# Memory_Address_Register_Connector.net
KiCad netlist of a schematic drawn in Altium Designer
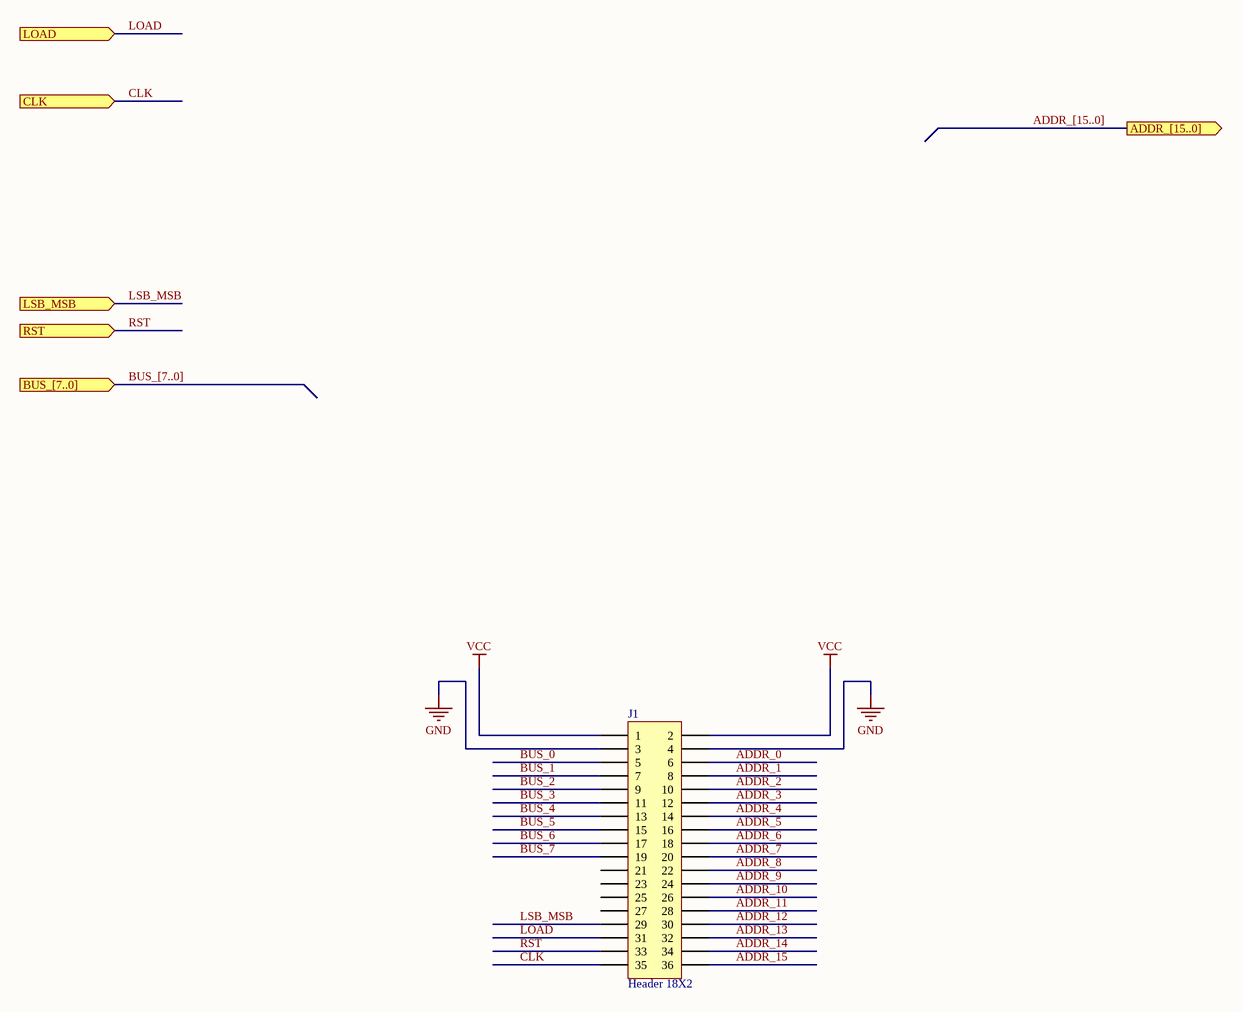
[diagram p0: Memory Address Register Connector.SchDoc]

(export (version "E")
  (design (tool "Eeschema 10.0.6"))
  (components
    (comp (ref "J1")
      (value "Header 18X2")
      (footprint "HDR2X18")
      (description "Header, 18-Pin, Dual row")
      (fields (field (name "PUBLISHER") "Altium Limited"))
      (libsource (lib "Miscellaneous Connectors") (part "Header 18X2"))
    )
  )
  (nets
    (net (code "1") (name "/ADDR_0") (class "Default")
      (node (ref "J1") (pin "6") (pinfunction "6_6") (pintype "passive"))
    )
    (net (code "2") (name "/ADDR_1") (class "Default")
      (node (ref "J1") (pin "8") (pinfunction "8_8") (pintype "passive"))
    )
    (net (code "3") (name "/ADDR_2") (class "Default")
      (node (ref "J1") (pin "10") (pinfunction "10_10") (pintype "passive"))
    )
    (net (code "4") (name "/ADDR_3") (class "Default")
      (node (ref "J1") (pin "12") (pinfunction "12_12") (pintype "passive"))
    )
    (net (code "5") (name "/ADDR_4") (class "Default")
      (node (ref "J1") (pin "14") (pinfunction "14_14") (pintype "passive"))
    )
    (net (code "6") (name "/ADDR_5") (class "Default")
      (node (ref "J1") (pin "16") (pinfunction "16_16") (pintype "passive"))
    )
    (net (code "7") (name "/ADDR_6") (class "Default")
      (node (ref "J1") (pin "18") (pinfunction "18_18") (pintype "passive"))
    )
    (net (code "8") (name "/ADDR_7") (class "Default")
      (node (ref "J1") (pin "20") (pinfunction "20_20") (pintype "passive"))
    )
    (net (code "9") (name "/ADDR_8") (class "Default")
      (node (ref "J1") (pin "22") (pinfunction "22_22") (pintype "passive"))
    )
    (net (code "10") (name "/ADDR_9") (class "Default")
      (node (ref "J1") (pin "24") (pinfunction "24_24") (pintype "passive"))
    )
    (net (code "11") (name "/ADDR_10") (class "Default")
      (node (ref "J1") (pin "26") (pinfunction "26_26") (pintype "passive"))
    )
    (net (code "12") (name "/ADDR_11") (class "Default")
      (node (ref "J1") (pin "28") (pinfunction "28_28") (pintype "passive"))
    )
    (net (code "13") (name "/ADDR_12") (class "Default")
      (node (ref "J1") (pin "30") (pinfunction "30_30") (pintype "passive"))
    )
    (net (code "14") (name "/ADDR_13") (class "Default")
      (node (ref "J1") (pin "32") (pinfunction "32_32") (pintype "passive"))
    )
    (net (code "15") (name "/ADDR_14") (class "Default")
      (node (ref "J1") (pin "34") (pinfunction "34_34") (pintype "passive"))
    )
    (net (code "16") (name "/ADDR_15") (class "Default")
      (node (ref "J1") (pin "36") (pinfunction "36_36") (pintype "passive"))
    )
    (net (code "18") (name "/BUS_0") (class "Default")
      (node (ref "J1") (pin "5") (pinfunction "5_5") (pintype "passive"))
    )
    (net (code "19") (name "/BUS_1") (class "Default")
      (node (ref "J1") (pin "7") (pinfunction "7_7") (pintype "passive"))
    )
    (net (code "20") (name "/BUS_2") (class "Default")
      (node (ref "J1") (pin "9") (pinfunction "9_9") (pintype "passive"))
    )
    (net (code "21") (name "/BUS_3") (class "Default")
      (node (ref "J1") (pin "11") (pinfunction "11_11") (pintype "passive"))
    )
    (net (code "22") (name "/BUS_4") (class "Default")
      (node (ref "J1") (pin "13") (pinfunction "13_13") (pintype "passive"))
    )
    (net (code "23") (name "/BUS_5") (class "Default")
      (node (ref "J1") (pin "15") (pinfunction "15_15") (pintype "passive"))
    )
    (net (code "24") (name "/BUS_6") (class "Default")
      (node (ref "J1") (pin "17") (pinfunction "17_17") (pintype "passive"))
    )
    (net (code "25") (name "/BUS_7") (class "Default")
      (node (ref "J1") (pin "19") (pinfunction "19_19") (pintype "passive"))
    )
    (net (code "27") (name "/CLK") (class "Default")
      (node (ref "J1") (pin "35") (pinfunction "35_35") (pintype "passive"))
    )
    (net (code "28") (name "/LOAD") (class "Default")
      (node (ref "J1") (pin "31") (pinfunction "31_31") (pintype "passive"))
    )
    (net (code "29") (name "/LSB_MSB") (class "Default")
      (node (ref "J1") (pin "29") (pinfunction "29_29") (pintype "passive"))
    )
    (net (code "30") (name "/RST") (class "Default")
      (node (ref "J1") (pin "33") (pinfunction "33_33") (pintype "passive"))
    )
    (net (code "31") (name "GND") (class "Default")
      (node (ref "J1") (pin "3") (pinfunction "3_3") (pintype "passive"))
      (node (ref "J1") (pin "4") (pinfunction "4_4") (pintype "passive"))
    )
    (net (code "32") (name "VCC") (class "Default")
      (node (ref "J1") (pin "1") (pinfunction "1_1") (pintype "passive"))
      (node (ref "J1") (pin "2") (pinfunction "2_2") (pintype "passive"))
    )
    (net (code "33") (name "unconnected-(J1-Pad21)") (class "Default")
      (node (ref "J1") (pin "21") (pinfunction "21_21") (pintype "passive"))
    )
    (net (code "34") (name "unconnected-(J1-Pad23)") (class "Default")
      (node (ref "J1") (pin "23") (pinfunction "23_23") (pintype "passive"))
    )
    (net (code "35") (name "unconnected-(J1-Pad25)") (class "Default")
      (node (ref "J1") (pin "25") (pinfunction "25_25") (pintype "passive"))
    )
    (net (code "36") (name "unconnected-(J1-Pad27)") (class "Default")
      (node (ref "J1") (pin "27") (pinfunction "27_27") (pintype "passive"))
    )
  )
)
